# VoltageBuffers.net
KiCad netlist of a schematic drawn in Altium Designer
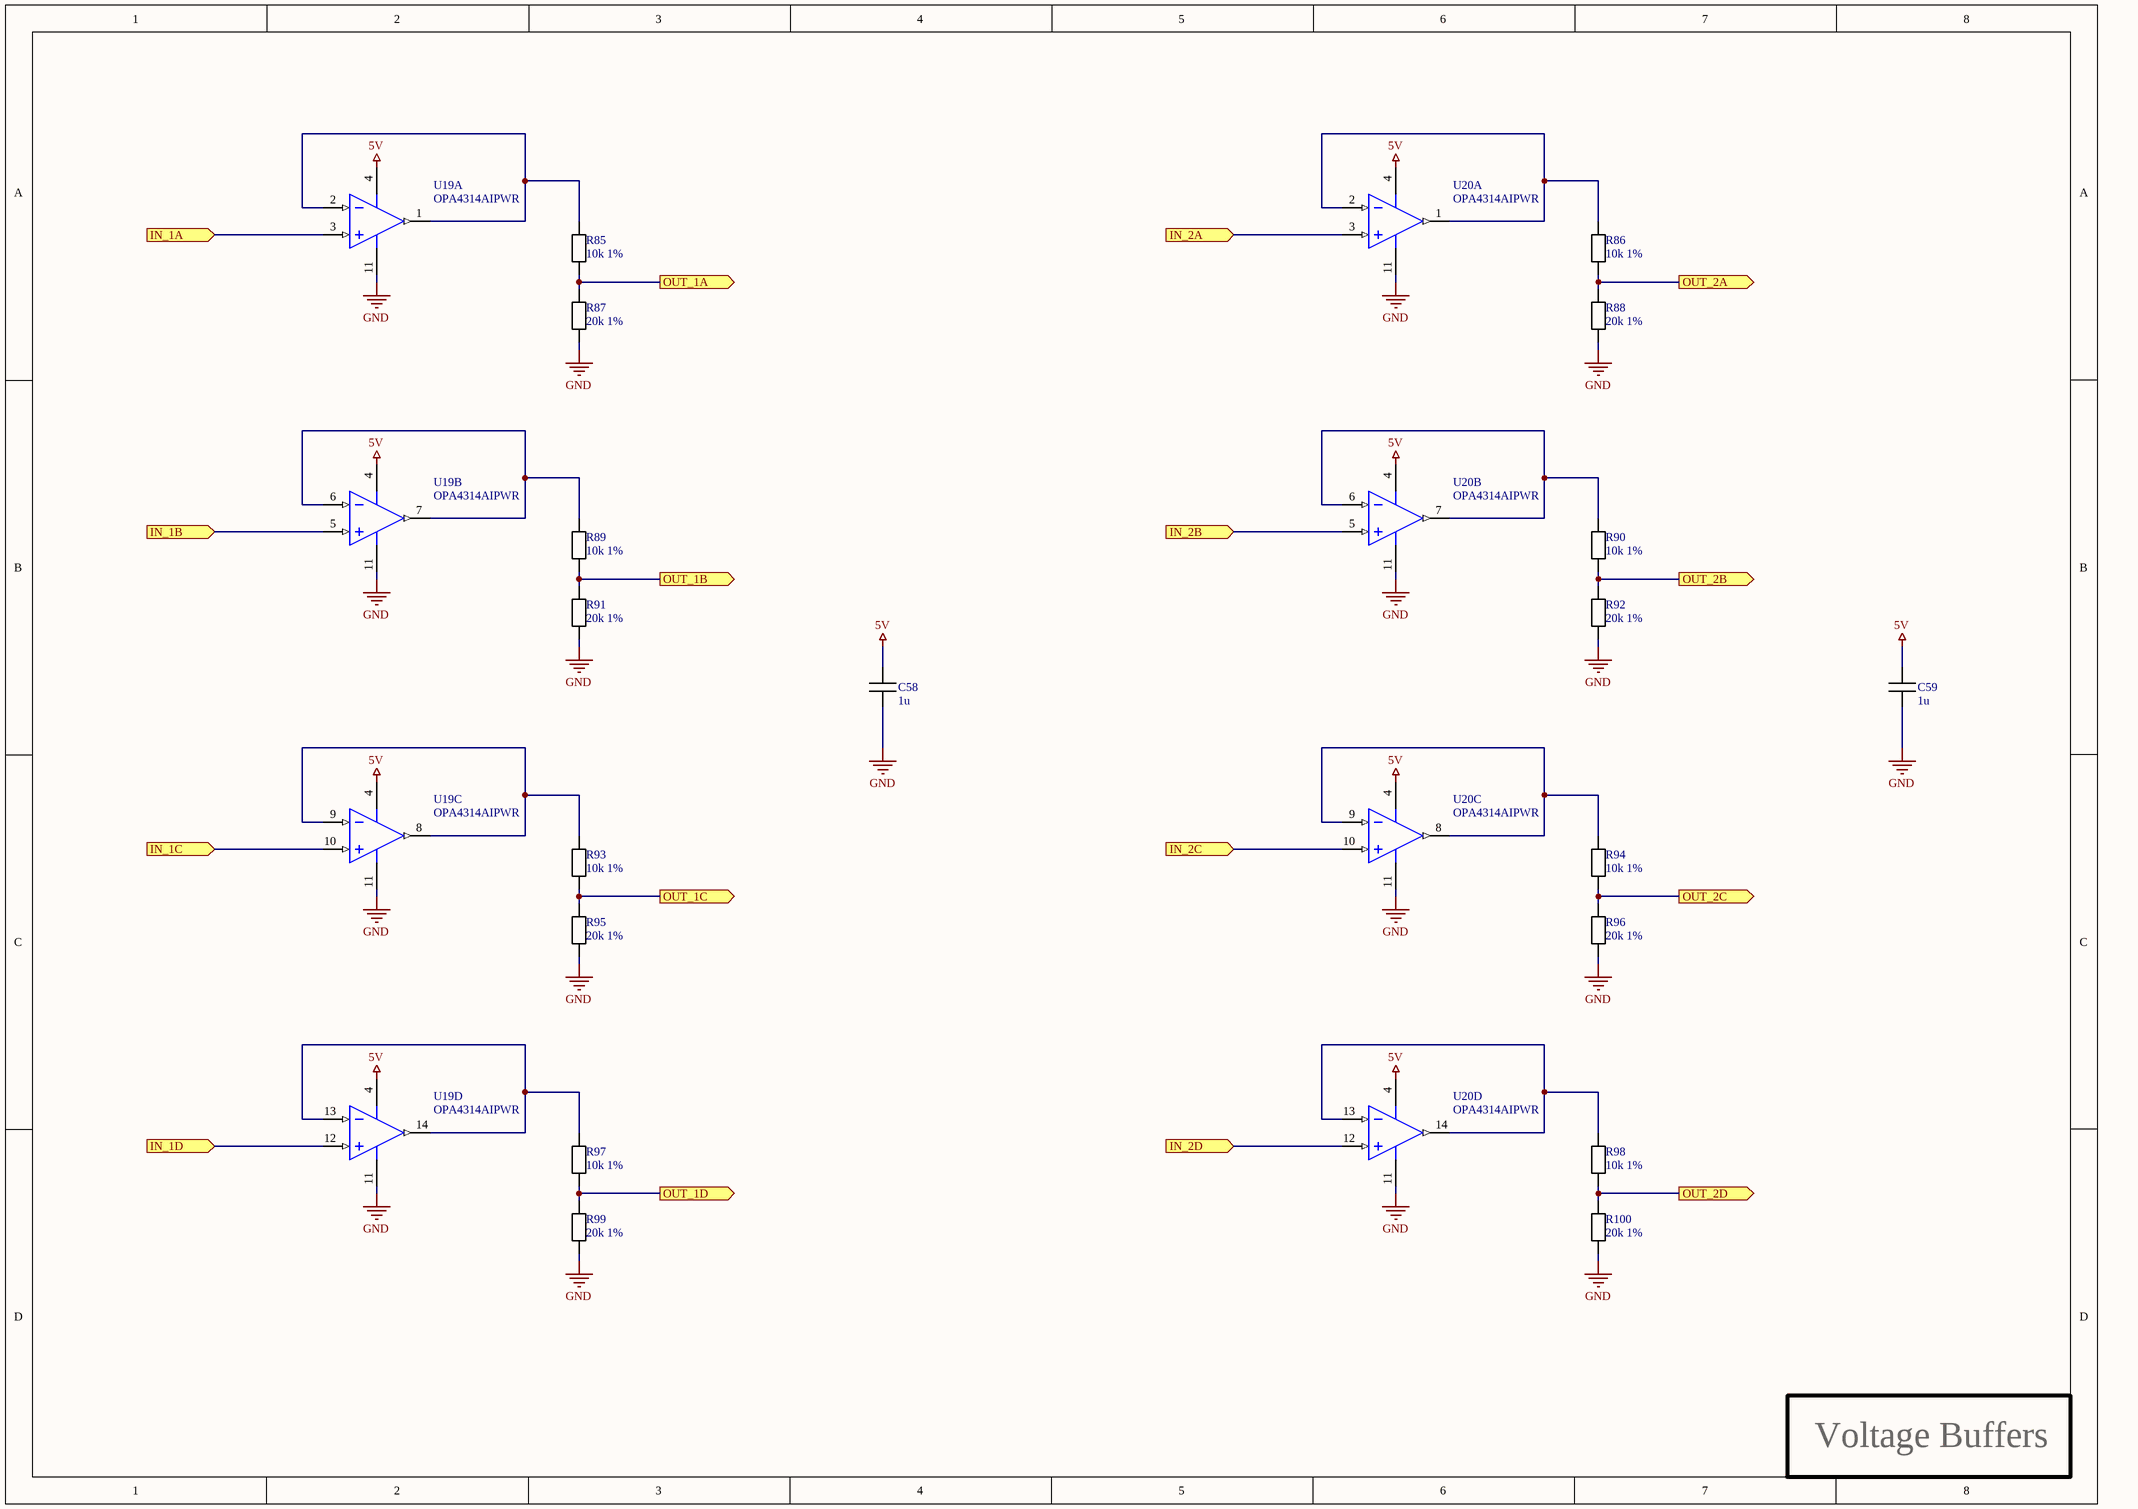
[diagram p0: VoltageBuffers.SchDoc]

(export (version "E")
  (design (tool "Eeschema 10.0.6"))
  (components
    (comp (ref "C58")
      (value "1u")
      (footprint "C_0603_AUTO")
      (fields (field (name "MANUFACTURER") "[Generic]"))
      (libsource (lib "GuowLib") (part "Capacitor"))
    )
    (comp (ref "C59")
      (value "1u")
      (footprint "C_0603_AUTO")
      (fields (field (name "MANUFACTURER") "[Generic]"))
      (libsource (lib "GuowLib") (part "Capacitor"))
    )
    (comp (ref "R85")
      (value "10k 1%")
      (footprint "R_0603_AUTO")
      (fields (field (name "MPN") "[Generic]"))
      (libsource (lib "GuowLib") (part "Resistor"))
    )
    (comp (ref "R86")
      (value "10k 1%")
      (footprint "R_0603_AUTO")
      (fields (field (name "MPN") "[Generic]"))
      (libsource (lib "GuowLib") (part "Resistor"))
    )
    (comp (ref "R87")
      (value "20k 1%")
      (footprint "R_0603_AUTO")
      (fields (field (name "MPN") "[Generic]"))
      (libsource (lib "GuowLib") (part "Resistor"))
    )
    (comp (ref "R88")
      (value "20k 1%")
      (footprint "R_0603_AUTO")
      (fields (field (name "MPN") "[Generic]"))
      (libsource (lib "GuowLib") (part "Resistor"))
    )
    (comp (ref "R89")
      (value "10k 1%")
      (footprint "R_0603_AUTO")
      (fields (field (name "MPN") "[Generic]"))
      (libsource (lib "GuowLib") (part "Resistor"))
    )
    (comp (ref "R90")
      (value "10k 1%")
      (footprint "R_0603_AUTO")
      (fields (field (name "MPN") "[Generic]"))
      (libsource (lib "GuowLib") (part "Resistor"))
    )
    (comp (ref "R91")
      (value "20k 1%")
      (footprint "R_0603_AUTO")
      (fields (field (name "MPN") "[Generic]"))
      (libsource (lib "GuowLib") (part "Resistor"))
    )
    (comp (ref "R92")
      (value "20k 1%")
      (footprint "R_0603_AUTO")
      (fields (field (name "MPN") "[Generic]"))
      (libsource (lib "GuowLib") (part "Resistor"))
    )
    (comp (ref "R93")
      (value "10k 1%")
      (footprint "R_0603_AUTO")
      (fields (field (name "MPN") "[Generic]"))
      (libsource (lib "GuowLib") (part "Resistor"))
    )
    (comp (ref "R94")
      (value "10k 1%")
      (footprint "R_0603_AUTO")
      (fields (field (name "MPN") "[Generic]"))
      (libsource (lib "GuowLib") (part "Resistor"))
    )
    (comp (ref "R95")
      (value "20k 1%")
      (footprint "R_0603_AUTO")
      (fields (field (name "MPN") "[Generic]"))
      (libsource (lib "GuowLib") (part "Resistor"))
    )
    (comp (ref "R96")
      (value "20k 1%")
      (footprint "R_0603_AUTO")
      (fields (field (name "MPN") "[Generic]"))
      (libsource (lib "GuowLib") (part "Resistor"))
    )
    (comp (ref "R97")
      (value "10k 1%")
      (footprint "R_0603_AUTO")
      (fields (field (name "MPN") "[Generic]"))
      (libsource (lib "GuowLib") (part "Resistor"))
    )
    (comp (ref "R98")
      (value "10k 1%")
      (footprint "R_0603_AUTO")
      (fields (field (name "MPN") "[Generic]"))
      (libsource (lib "GuowLib") (part "Resistor"))
    )
    (comp (ref "R99")
      (value "20k 1%")
      (footprint "R_0603_AUTO")
      (fields (field (name "MPN") "[Generic]"))
      (libsource (lib "GuowLib") (part "Resistor"))
    )
    (comp (ref "R100")
      (value "20k 1%")
      (footprint "R_0603_AUTO")
      (fields (field (name "MPN") "[Generic]"))
      (libsource (lib "GuowLib") (part "Resistor"))
    )
    (comp (ref "U19")
      (value "OPA4314AIPWR")
      (footprint "PW0014A_N")
      (fields (field (name "MANUFACTURER") "Texas Instruments"))
      (libsource (lib "Altium Content Vault") (part "TI-OPA16X4_4XXX-14"))
    )
    (comp (ref "U20")
      (value "OPA4314AIPWR")
      (footprint "PW0014A_N")
      (fields (field (name "MANUFACTURER") "Texas Instruments"))
      (libsource (lib "Altium Content Vault") (part "TI-OPA16X4_4XXX-14"))
    )
  )
  (nets
    (net (code "1") (name "/IN_1A") (class "Default")
      (node (ref "U19") (pin "3") (pinfunction "IN_A+_3") (pintype "input"))
    )
    (net (code "2") (name "/IN_1B") (class "Default")
      (node (ref "U19") (pin "5") (pinfunction "IN_B+_5") (pintype "input"))
    )
    (net (code "3") (name "/IN_1C") (class "Default")
      (node (ref "U19") (pin "10") (pinfunction "IN_C+_10") (pintype "input"))
    )
    (net (code "4") (name "/IN_1D") (class "Default")
      (node (ref "U19") (pin "12") (pinfunction "IN_D+_12") (pintype "input"))
    )
    (net (code "5") (name "/IN_2A") (class "Default")
      (node (ref "U20") (pin "3") (pinfunction "IN_A+_3") (pintype "input"))
    )
    (net (code "6") (name "/IN_2B") (class "Default")
      (node (ref "U20") (pin "5") (pinfunction "IN_B+_5") (pintype "input"))
    )
    (net (code "7") (name "/IN_2C") (class "Default")
      (node (ref "U20") (pin "10") (pinfunction "IN_C+_10") (pintype "input"))
    )
    (net (code "8") (name "/IN_2D") (class "Default")
      (node (ref "U20") (pin "12") (pinfunction "IN_D+_12") (pintype "input"))
    )
    (net (code "9") (name "/OUT_1A") (class "Default")
      (node (ref "R85") (pin "1") (pinfunction "1_1") (pintype "passive"))
      (node (ref "R87") (pin "2") (pinfunction "2_2") (pintype "passive"))
    )
    (net (code "10") (name "/OUT_1B") (class "Default")
      (node (ref "R89") (pin "1") (pinfunction "1_1") (pintype "passive"))
      (node (ref "R91") (pin "2") (pinfunction "2_2") (pintype "passive"))
    )
    (net (code "11") (name "/OUT_1C") (class "Default")
      (node (ref "R93") (pin "1") (pinfunction "1_1") (pintype "passive"))
      (node (ref "R95") (pin "2") (pinfunction "2_2") (pintype "passive"))
    )
    (net (code "12") (name "/OUT_1D") (class "Default")
      (node (ref "R97") (pin "1") (pinfunction "1_1") (pintype "passive"))
      (node (ref "R99") (pin "2") (pinfunction "2_2") (pintype "passive"))
    )
    (net (code "13") (name "/OUT_2A") (class "Default")
      (node (ref "R86") (pin "1") (pinfunction "1_1") (pintype "passive"))
      (node (ref "R88") (pin "2") (pinfunction "2_2") (pintype "passive"))
    )
    (net (code "14") (name "/OUT_2B") (class "Default")
      (node (ref "R90") (pin "1") (pinfunction "1_1") (pintype "passive"))
      (node (ref "R92") (pin "2") (pinfunction "2_2") (pintype "passive"))
    )
    (net (code "15") (name "/OUT_2C") (class "Default")
      (node (ref "R94") (pin "1") (pinfunction "1_1") (pintype "passive"))
      (node (ref "R96") (pin "2") (pinfunction "2_2") (pintype "passive"))
    )
    (net (code "16") (name "/OUT_2D") (class "Default")
      (node (ref "R100") (pin "2") (pinfunction "2_2") (pintype "passive"))
      (node (ref "R98") (pin "1") (pinfunction "1_1") (pintype "passive"))
    )
    (net (code "17") (name "5V") (class "Default")
      (node (ref "C58") (pin "2") (pinfunction "2_2") (pintype "passive"))
      (node (ref "C59") (pin "2") (pinfunction "2_2") (pintype "passive"))
      (node (ref "U19") (pin "4") (pinfunction "V+_4") (pintype "power_in"))
      (node (ref "U20") (pin "4") (pinfunction "V+_4") (pintype "power_in"))
    )
    (net (code "18") (name "GND") (class "Default")
      (node (ref "C58") (pin "1") (pinfunction "1_1") (pintype "passive"))
      (node (ref "C59") (pin "1") (pinfunction "1_1") (pintype "passive"))
      (node (ref "R100") (pin "1") (pinfunction "1_1") (pintype "passive"))
      (node (ref "R87") (pin "1") (pinfunction "1_1") (pintype "passive"))
      (node (ref "R88") (pin "1") (pinfunction "1_1") (pintype "passive"))
      (node (ref "R91") (pin "1") (pinfunction "1_1") (pintype "passive"))
      (node (ref "R92") (pin "1") (pinfunction "1_1") (pintype "passive"))
      (node (ref "R95") (pin "1") (pinfunction "1_1") (pintype "passive"))
      (node (ref "R96") (pin "1") (pinfunction "1_1") (pintype "passive"))
      (node (ref "R99") (pin "1") (pinfunction "1_1") (pintype "passive"))
      (node (ref "U19") (pin "11") (pinfunction "V-_11") (pintype "power_in"))
      (node (ref "U20") (pin "11") (pinfunction "V-_11") (pintype "power_in"))
    )
    (net (code "19") (name "Net-(U19A-IN_A-)") (class "Default")
      (node (ref "R85") (pin "2") (pinfunction "2_2") (pintype "passive"))
      (node (ref "U19") (pin "1") (pinfunction "OUT_A_1") (pintype "output"))
      (node (ref "U19") (pin "2") (pinfunction "IN_A-_2") (pintype "input"))
    )
    (net (code "20") (name "Net-(U19B-IN_B-)") (class "Default")
      (node (ref "R89") (pin "2") (pinfunction "2_2") (pintype "passive"))
      (node (ref "U19") (pin "6") (pinfunction "IN_B-_6") (pintype "input"))
      (node (ref "U19") (pin "7") (pinfunction "OUT_B_7") (pintype "output"))
    )
    (net (code "21") (name "Net-(U19C-IN_C-)") (class "Default")
      (node (ref "R93") (pin "2") (pinfunction "2_2") (pintype "passive"))
      (node (ref "U19") (pin "8") (pinfunction "OUT_C_8") (pintype "output"))
      (node (ref "U19") (pin "9") (pinfunction "IN_C-_9") (pintype "input"))
    )
    (net (code "22") (name "Net-(U19D-IN_D-)") (class "Default")
      (node (ref "R97") (pin "2") (pinfunction "2_2") (pintype "passive"))
      (node (ref "U19") (pin "13") (pinfunction "IN_D-_13") (pintype "input"))
      (node (ref "U19") (pin "14") (pinfunction "OUT_D_14") (pintype "output"))
    )
    (net (code "23") (name "Net-(U20A-IN_A-)") (class "Default")
      (node (ref "R86") (pin "2") (pinfunction "2_2") (pintype "passive"))
      (node (ref "U20") (pin "1") (pinfunction "OUT_A_1") (pintype "output"))
      (node (ref "U20") (pin "2") (pinfunction "IN_A-_2") (pintype "input"))
    )
    (net (code "24") (name "Net-(U20B-IN_B-)") (class "Default")
      (node (ref "R90") (pin "2") (pinfunction "2_2") (pintype "passive"))
      (node (ref "U20") (pin "6") (pinfunction "IN_B-_6") (pintype "input"))
      (node (ref "U20") (pin "7") (pinfunction "OUT_B_7") (pintype "output"))
    )
    (net (code "25") (name "Net-(U20C-IN_C-)") (class "Default")
      (node (ref "R94") (pin "2") (pinfunction "2_2") (pintype "passive"))
      (node (ref "U20") (pin "8") (pinfunction "OUT_C_8") (pintype "output"))
      (node (ref "U20") (pin "9") (pinfunction "IN_C-_9") (pintype "input"))
    )
    (net (code "26") (name "Net-(U20D-IN_D-)") (class "Default")
      (node (ref "R98") (pin "2") (pinfunction "2_2") (pintype "passive"))
      (node (ref "U20") (pin "13") (pinfunction "IN_D-_13") (pintype "input"))
      (node (ref "U20") (pin "14") (pinfunction "OUT_D_14") (pintype "output"))
    )
  )
)
